# INVERTER_USE_555_IC.net
KiCad netlist of a schematic drawn in Altium Designer
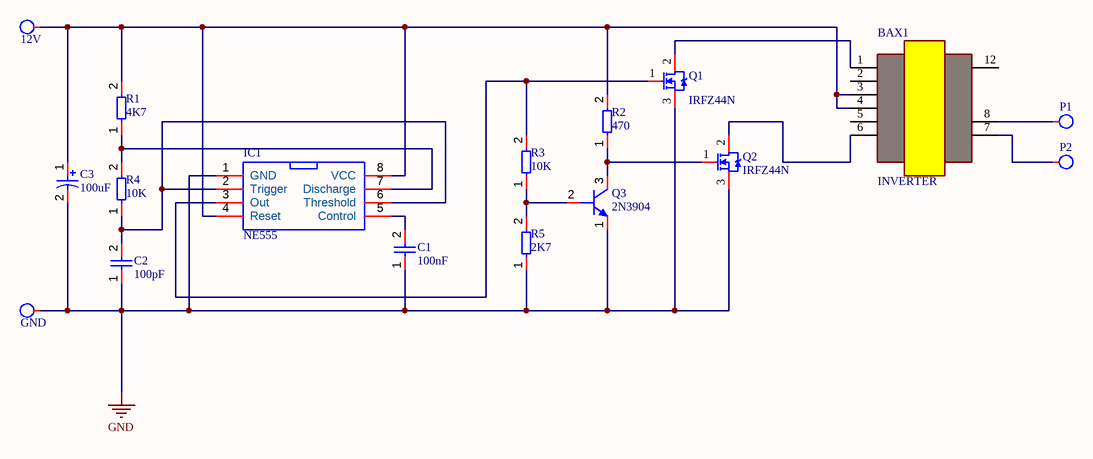
[diagram p0: INVERTER_USE_555_IC.SchDoc]

(export (version "E")
  (design (tool "Eeschema 10.0.6"))
  (components
    (comp (ref "12V")
      (value "SolderPoint")
      (footprint "SolderPoint")
      (libsource (lib "Lib31082020") (part "SolderPoint"))
    )
    (comp (ref "BAX1")
      (value "INVERTER")
      (footprint "BAX_INVERTER")
      (libsource (lib "Library 3D") (part "BAX_INVERTER"))
    )
    (comp (ref "C1")
      (value "100nF")
      (footprint "CAP_Ceramic_Disc_2")
      (libsource (lib "Lib31082020") (part "Capacitors(Disc)"))
    )
    (comp (ref "C2")
      (value "100pF")
      (footprint "CAP_Ceramic_Disc_2")
      (libsource (lib "Lib31082020") (part "Capacitors(Disc)"))
    )
    (comp (ref "C3")
      (value "100uF")
      (footprint "CAP_RAD_5mm")
      (libsource (lib "Lib31082020") (part "Capacitor(Radian)"))
    )
    (comp (ref "GND")
      (value "SolderPoint")
      (footprint "SolderPoint")
      (libsource (lib "Lib31082020") (part "SolderPoint"))
    )
    (comp (ref "IC1") (value "NE555") (footprint "N08E_TEX") (libsource (lib "Lib31082020") (part "NE555")))
    (comp (ref "P1")
      (value "SolderPoint")
      (footprint "SolderPoint")
      (libsource (lib "Lib31082020") (part "SolderPoint"))
    )
    (comp (ref "P2")
      (value "SolderPoint")
      (footprint "SolderPoint")
      (libsource (lib "Lib31082020") (part "SolderPoint"))
    )
    (comp (ref "Q1") (value "IRFZ44N") (footprint "TO-220A") (libsource (lib "Lib31082020") (part "IRFZ44N")))
    (comp (ref "Q2") (value "IRFZ44N") (footprint "TO-220A") (libsource (lib "Lib31082020") (part "IRFZ44N")))
    (comp (ref "Q3")
      (value "2N3904")
      (footprint "TO-92")
      (libsource (lib "Lib31082020") (part "2N3904 (TO-92)"))
    )
    (comp (ref "R1")
      (value "4K7")
      (footprint "RES-0.25W-H-MF")
      (libsource (lib "Lib31082020") (part "Resistors THD"))
    )
    (comp (ref "R2")
      (value "470")
      (footprint "RES-0.25W-H-MF")
      (libsource (lib "Lib31082020") (part "Resistors THD"))
    )
    (comp (ref "R3")
      (value "10K")
      (footprint "RES-0.25W-H-MF")
      (libsource (lib "Lib31082020") (part "Resistors THD"))
    )
    (comp (ref "R4")
      (value "10K")
      (footprint "RES-0.25W-H-MF")
      (libsource (lib "Lib31082020") (part "Resistors THD"))
    )
    (comp (ref "R5")
      (value "2K7")
      (footprint "RES-0.25W-H-MF")
      (libsource (lib "Lib31082020") (part "Resistors THD"))
    )
  )
  (nets
    (net (code "1") (name "GND") (class "Default")
      (node (ref "C1") (pin "1") (pinfunction "1_1") (pintype "passive"))
      (node (ref "C2") (pin "1") (pinfunction "1_1") (pintype "passive"))
      (node (ref "C3") (pin "2") (pinfunction "2_2") (pintype "passive"))
      (node (ref "GND") (pin "1") (pinfunction "1_1") (pintype "passive"))
      (node (ref "IC1") (pin "1") (pinfunction "GND_1") (pintype "passive"))
      (node (ref "Q1") (pin "3") (pinfunction "S_3") (pintype "passive"))
      (node (ref "Q2") (pin "3") (pinfunction "S_3") (pintype "passive"))
      (node (ref "Q3") (pin "1") (pinfunction "E_1") (pintype "passive"))
      (node (ref "R5") (pin "1") (pinfunction "1_1") (pintype "passive"))
    )
    (net (code "2") (name "Net-(BAX1-Pad7)") (class "Default")
      (node (ref "BAX1") (pin "7") (pinfunction "7_7") (pintype "passive"))
      (node (ref "P2") (pin "1") (pinfunction "1_1") (pintype "passive"))
    )
    (net (code "3") (name "Net-(BAX1-Pad8)") (class "Default")
      (node (ref "BAX1") (pin "8") (pinfunction "8_8") (pintype "passive"))
      (node (ref "P1") (pin "1") (pinfunction "1_1") (pintype "passive"))
    )
    (net (code "4") (name "Net-(IC1-Control)") (class "Default")
      (node (ref "C1") (pin "2") (pinfunction "2_2") (pintype "passive"))
      (node (ref "IC1") (pin "5") (pinfunction "Control_5") (pintype "passive"))
    )
    (net (code "5") (name "Net-(IC1-Discharge)") (class "Default")
      (node (ref "IC1") (pin "7") (pinfunction "Discharge_7") (pintype "passive"))
      (node (ref "R1") (pin "1") (pinfunction "1_1") (pintype "passive"))
      (node (ref "R4") (pin "2") (pinfunction "2_2") (pintype "passive"))
    )
    (net (code "6") (name "Net-(IC1-Out)") (class "Default")
      (node (ref "IC1") (pin "3") (pinfunction "Out_3") (pintype "passive"))
      (node (ref "Q1") (pin "1") (pinfunction "G_1") (pintype "passive"))
      (node (ref "R3") (pin "2") (pinfunction "2_2") (pintype "passive"))
    )
    (net (code "7") (name "Net-(IC1-Reset)") (class "Default")
      (node (ref "12V") (pin "1") (pinfunction "1_1") (pintype "passive"))
      (node (ref "BAX1") (pin "3") (pinfunction "3_3") (pintype "passive"))
      (node (ref "BAX1") (pin "4") (pinfunction "4_4") (pintype "passive"))
      (node (ref "C3") (pin "1") (pinfunction "1_1") (pintype "passive"))
      (node (ref "IC1") (pin "4") (pinfunction "Reset_4") (pintype "passive"))
      (node (ref "IC1") (pin "8") (pinfunction "VCC_8") (pintype "passive"))
      (node (ref "R1") (pin "2") (pinfunction "2_2") (pintype "passive"))
      (node (ref "R2") (pin "2") (pinfunction "2_2") (pintype "passive"))
    )
    (net (code "8") (name "Net-(IC1-Threshold)") (class "Default")
      (node (ref "C2") (pin "2") (pinfunction "2_2") (pintype "passive"))
      (node (ref "IC1") (pin "2") (pinfunction "Trigger_2") (pintype "passive"))
      (node (ref "IC1") (pin "6") (pinfunction "Threshold_6") (pintype "passive"))
      (node (ref "R4") (pin "1") (pinfunction "1_1") (pintype "passive"))
    )
    (net (code "9") (name "Net-(Q1-D)") (class "Default")
      (node (ref "BAX1") (pin "1") (pinfunction "1_1") (pintype "passive"))
      (node (ref "Q1") (pin "2") (pinfunction "D_2") (pintype "passive"))
    )
    (net (code "10") (name "Net-(Q2-D)") (class "Default")
      (node (ref "BAX1") (pin "6") (pinfunction "6_6") (pintype "passive"))
      (node (ref "Q2") (pin "2") (pinfunction "D_2") (pintype "passive"))
    )
    (net (code "11") (name "Net-(Q2-G)") (class "Default")
      (node (ref "Q2") (pin "1") (pinfunction "G_1") (pintype "passive"))
      (node (ref "Q3") (pin "3") (pinfunction "C_3") (pintype "passive"))
      (node (ref "R2") (pin "1") (pinfunction "1_1") (pintype "passive"))
    )
    (net (code "12") (name "Net-(Q3-B)") (class "Default")
      (node (ref "Q3") (pin "2") (pinfunction "B_2") (pintype "passive"))
      (node (ref "R3") (pin "1") (pinfunction "1_1") (pintype "passive"))
      (node (ref "R5") (pin "2") (pinfunction "2_2") (pintype "passive"))
    )
    (net (code "13") (name "unconnected-(BAX1-Pad2)") (class "Default")
      (node (ref "BAX1") (pin "2") (pinfunction "2_2") (pintype "passive"))
    )
    (net (code "14") (name "unconnected-(BAX1-Pad5)") (class "Default")
      (node (ref "BAX1") (pin "5") (pinfunction "5_5") (pintype "passive"))
    )
    (net (code "15") (name "unconnected-(BAX1-Pad12)") (class "Default")
      (node (ref "BAX1") (pin "12") (pinfunction "12_12") (pintype "passive"))
    )
  )
)
